# untitled.net
KiCad netlist of a schematic drawn in EAGLE
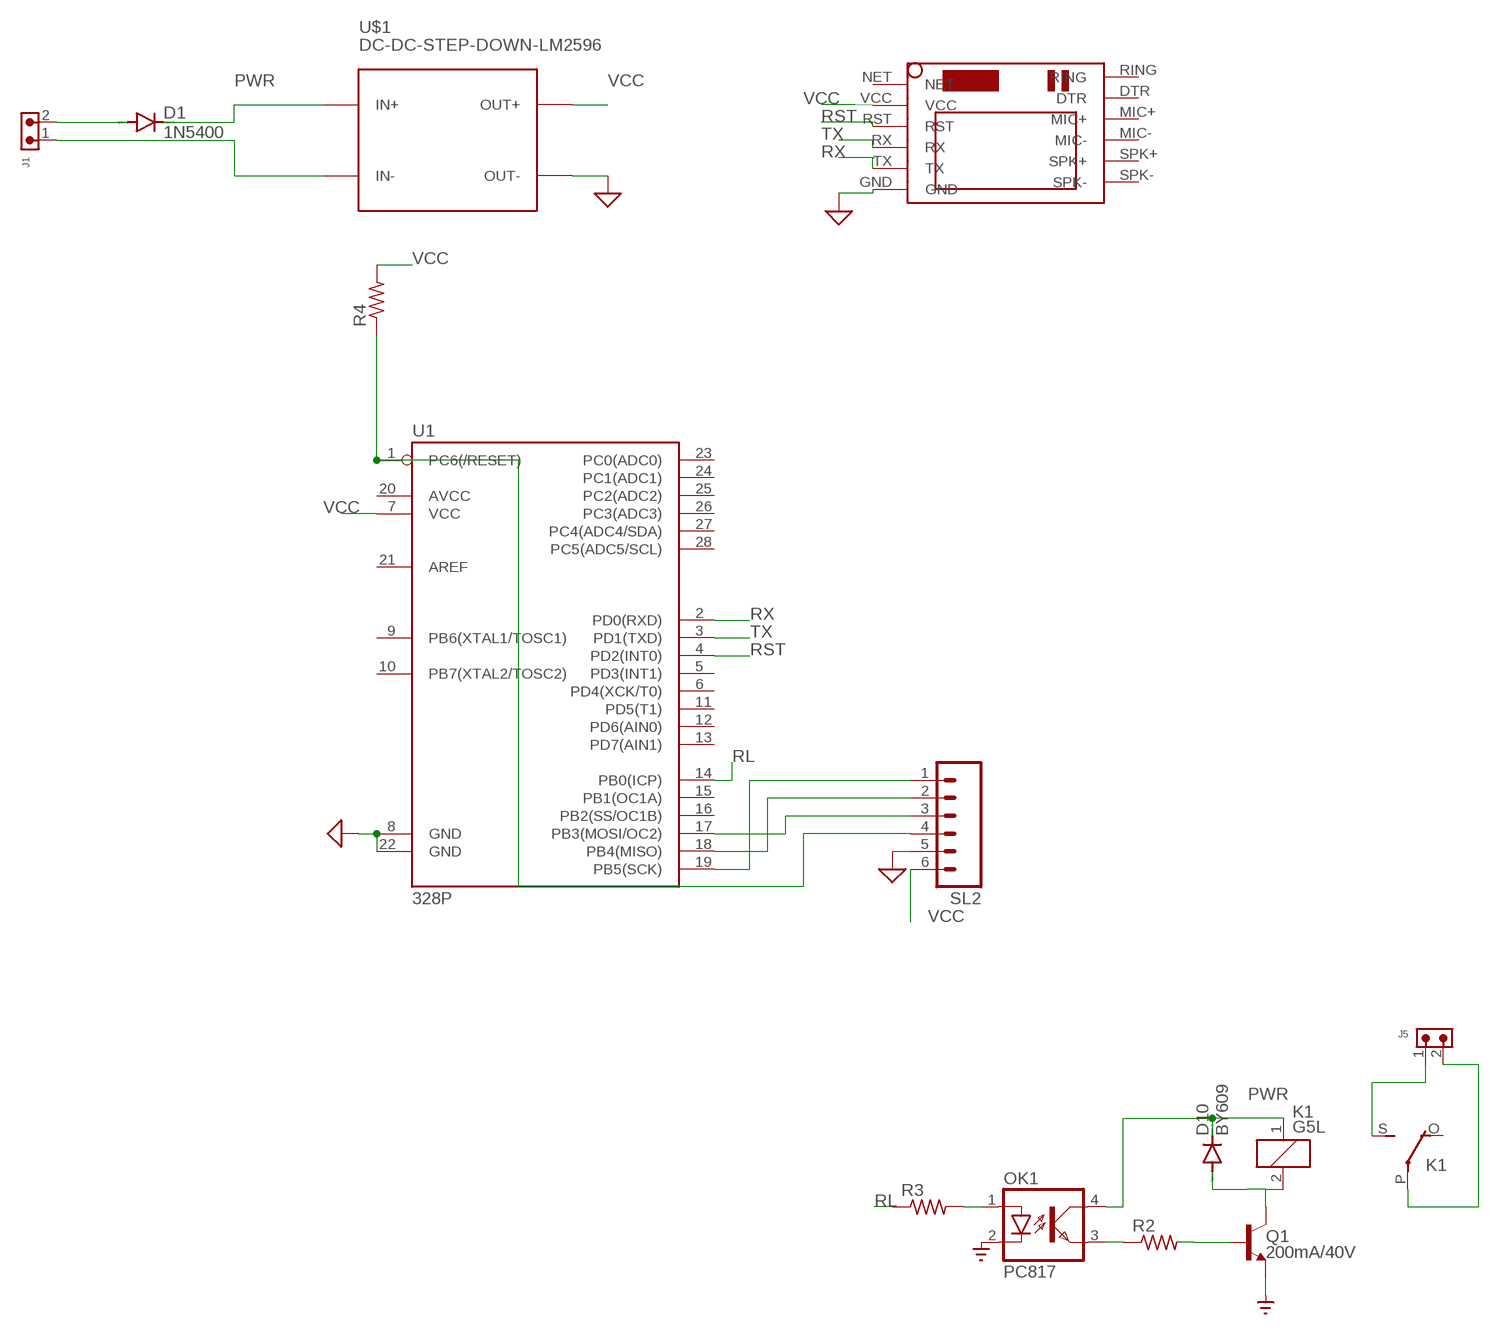
[diagram p0: schematic, sheet 1]

(export (version "E")
  (design (tool "Eeschema 10.0.6"))
  (components
    (comp (ref "D1")
      (value "1N5400")
      (footprint "eagle-import:DO201-15")
      (libsource (lib "eagle-import") (part "1N5400"))
    )
    (comp (ref "D10")
      (value "BY609")
      (footprint "eagle-import:SOD61B")
      (libsource (lib "eagle-import") (part "BY609"))
    )
    (comp (ref "J1")
      (value "691305530002")
      (footprint "eagle-import:691305530002")
      (libsource (lib "eagle-import") (part "691305530002"))
    )
    (comp (ref "J5")
      (value "691305530002")
      (footprint "eagle-import:691305530002")
      (libsource (lib "eagle-import") (part "691305530002"))
    )
    (comp (ref "K1")
      (value "G5L")
      (footprint "eagle-import:G5LE")
      (libsource (lib "eagle-import") (part "G5L"))
    )
    (comp (ref "OK1")
      (value "PC817")
      (footprint "eagle-import:DIL04")
      (fields (field (name "MPN") "PC817X4J000F"))
      (libsource (lib "eagle-import") (part "PC817"))
    )
    (comp (ref "Q1")
      (value "200mA/40V")
      (footprint "eagle-import:TO-92")
      (libsource (lib "eagle-import") (part "TRANS_NPN-2N3904"))
    )
    (comp (ref "R2")
      (value "R-US_0207/10")
      (footprint "eagle-import:0207_10")
      (libsource (lib "eagle-import") (part "R-US_0207/10"))
    )
    (comp (ref "R3")
      (value "R-US_0207/7")
      (footprint "eagle-import:0207_7")
      (libsource (lib "eagle-import") (part "adafruit_R-US_0207/7"))
    )
    (comp (ref "R4")
      (value "R-US_0207/10")
      (footprint "eagle-import:0207_10")
      (libsource (lib "eagle-import") (part "R-US_0207/10"))
    )
    (comp (ref "SL2")
      (value "M06")
      (footprint "eagle-import:06P")
      (libsource (lib "eagle-import") (part "M06"))
    )
    (comp (ref "U$1")
      (value "DC-DC-STEP-DOWN-LM2596")
      (footprint "eagle-import:DC-DC-STEP-DOWN-LM2596")
      (libsource (lib "eagle-import") (part "DC-DC-STEP-DOWN-LM2596"))
    )
    (comp (ref "U$2")
      (value "SIM800LMODULE")
      (footprint "eagle-import:SIM800LMODULE")
      (libsource (lib "eagle-import") (part "SIM800LMODULE"))
    )
    (comp (ref "U1")
      (value "328P")
      (footprint "eagle-import:DIP28")
      (libsource (lib "eagle-import") (part "ATMEGA328P_PDIP"))
    )
  )
  (nets
    (net (code "1") (name "/PWR") (class "Default")
      (node (ref "D1") (pin "C") (pinfunction "C_C") (pintype "passive"))
      (node (ref "D10") (pin "C") (pinfunction "C_C") (pintype "passive"))
      (node (ref "K1") (pin "1") (pinfunction "1_1") (pintype "passive"))
      (node (ref "OK1") (pin "4") (pinfunction "COL_4") (pintype "passive"))
      (node (ref "U$1") (pin "IN+") (pinfunction "IN+_IN+") (pintype "bidirectional"))
    )
    (net (code "2") (name "/RL") (class "Default")
      (node (ref "R3") (pin "1") (pinfunction "1_1") (pintype "passive"))
      (node (ref "U1") (pin "14") (pinfunction "PB0(ICP)_14") (pintype "bidirectional"))
    )
    (net (code "3") (name "/RST") (class "Default")
      (node (ref "U$2") (pin "RST") (pinfunction "RST_RST") (pintype "bidirectional"))
      (node (ref "U1") (pin "4") (pinfunction "PD2(INT0)_4") (pintype "bidirectional"))
    )
    (net (code "4") (name "/RX") (class "Default")
      (node (ref "U$2") (pin "TX") (pinfunction "TX_TX") (pintype "bidirectional"))
      (node (ref "U1") (pin "2") (pinfunction "PD0(RXD)_2") (pintype "bidirectional"))
    )
    (net (code "5") (name "/TX") (class "Default")
      (node (ref "U$2") (pin "RX") (pinfunction "RX_RX") (pintype "bidirectional"))
      (node (ref "U1") (pin "3") (pinfunction "PD1(TXD)_3") (pintype "bidirectional"))
    )
    (net (code "6") (name "/VCC") (class "Default")
      (node (ref "R4") (pin "2") (pinfunction "2_2") (pintype "passive"))
      (node (ref "SL2") (pin "6") (pinfunction "6_6") (pintype "passive"))
      (node (ref "U$1") (pin "OUT+") (pinfunction "OUT+_OUT+") (pintype "bidirectional"))
      (node (ref "U$2") (pin "VCC") (pinfunction "VCC_VCC") (pintype "bidirectional"))
      (node (ref "U1") (pin "7") (pinfunction "VCC_7") (pintype "bidirectional"))
    )
    (net (code "7") (name "Net-(D1-PadA)") (class "Default")
      (node (ref "D1") (pin "A") (pinfunction "A_A") (pintype "passive"))
      (node (ref "J1") (pin "2") (pinfunction "2_2") (pintype "passive"))
    )
    (net (code "8") (name "Net-(J1-Pad1)") (class "Default")
      (node (ref "J1") (pin "1") (pinfunction "1_1") (pintype "passive"))
      (node (ref "U$1") (pin "IN-") (pinfunction "IN-_IN-") (pintype "bidirectional"))
    )
    (net (code "9") (name "Net-(J5-Pad1)") (class "Default")
      (node (ref "J5") (pin "1") (pinfunction "1_1") (pintype "passive"))
      (node (ref "K1") (pin "S") (pinfunction "S_S") (pintype "passive"))
    )
    (net (code "10") (name "Net-(J5-Pad2)") (class "Default")
      (node (ref "J5") (pin "2") (pinfunction "2_2") (pintype "passive"))
      (node (ref "K1") (pin "P") (pinfunction "P_P") (pintype "passive"))
    )
    (net (code "11") (name "Net-(OK1-A)") (class "Default")
      (node (ref "OK1") (pin "1") (pinfunction "A_1") (pintype "passive"))
      (node (ref "R3") (pin "2") (pinfunction "2_2") (pintype "passive"))
    )
    (net (code "12") (name "Net-(OK1-EMIT)") (class "Default")
      (node (ref "OK1") (pin "3") (pinfunction "EMIT_3") (pintype "passive"))
      (node (ref "R2") (pin "1") (pinfunction "1_1") (pintype "passive"))
    )
    (net (code "13") (name "Net-(Q1-B)") (class "Default")
      (node (ref "Q1") (pin "2") (pinfunction "B_2") (pintype "passive"))
      (node (ref "R2") (pin "2") (pinfunction "2_2") (pintype "passive"))
    )
    (net (code "14") (name "Net-(Q1-C)") (class "Default")
      (node (ref "D10") (pin "A") (pinfunction "A_A") (pintype "passive"))
      (node (ref "K1") (pin "2") (pinfunction "2_2") (pintype "passive"))
      (node (ref "Q1") (pin "3") (pinfunction "C_3") (pintype "passive"))
    )
    (net (code "15") (name "Net-(U1-PB3(MOSI{slash}OC2))") (class "Default")
      (node (ref "SL2") (pin "3") (pinfunction "3_3") (pintype "passive"))
      (node (ref "U1") (pin "17") (pinfunction "PB3(MOSI/OC2)_17") (pintype "bidirectional"))
    )
    (net (code "16") (name "Net-(U1-PB4(MISO))") (class "Default")
      (node (ref "SL2") (pin "2") (pinfunction "2_2") (pintype "passive"))
      (node (ref "U1") (pin "18") (pinfunction "PB4(MISO)_18") (pintype "bidirectional"))
    )
    (net (code "17") (name "Net-(U1-PB5(SCK))") (class "Default")
      (node (ref "SL2") (pin "1") (pinfunction "1_1") (pintype "passive"))
      (node (ref "U1") (pin "19") (pinfunction "PB5(SCK)_19") (pintype "bidirectional"))
    )
    (net (code "18") (name "Net-(U1-PC6({slash}RESET))") (class "Default")
      (node (ref "R4") (pin "1") (pinfunction "1_1") (pintype "passive"))
      (node (ref "SL2") (pin "4") (pinfunction "4_4") (pintype "passive"))
      (node (ref "U1") (pin "1") (pinfunction "PC6(/RESET)_1") (pintype "bidirectional"))
    )
    (net (code "19") (name "SUP") (class "Default")
      (node (ref "OK1") (pin "2") (pinfunction "C_2") (pintype "passive"))
      (node (ref "Q1") (pin "1") (pinfunction "E_1") (pintype "passive"))
      (node (ref "SL2") (pin "5") (pinfunction "5_5") (pintype "passive"))
      (node (ref "U$1") (pin "OUT-") (pinfunction "OUT-_OUT-") (pintype "bidirectional"))
      (node (ref "U$2") (pin "GND") (pinfunction "GND_GND") (pintype "bidirectional"))
      (node (ref "U1") (pin "22") (pinfunction "GND_22") (pintype "bidirectional"))
      (node (ref "U1") (pin "8") (pinfunction "GND_8") (pintype "bidirectional"))
    )
    (net (code "20") (name "unconnected-(K1-PadO)") (class "Default")
      (node (ref "K1") (pin "O") (pinfunction "O_O") (pintype "passive"))
    )
    (net (code "21") (name "unconnected-(U$2-PadDTR)") (class "Default")
      (node (ref "U$2") (pin "DTR") (pinfunction "DTR_DTR") (pintype "bidirectional"))
    )
    (net (code "22") (name "unconnected-(U$2-PadMIC+)") (class "Default")
      (node (ref "U$2") (pin "MIC+") (pinfunction "MIC+_MIC+") (pintype "bidirectional"))
    )
    (net (code "23") (name "unconnected-(U$2-PadMIC-)") (class "Default")
      (node (ref "U$2") (pin "MIC-") (pinfunction "MIC-_MIC-") (pintype "bidirectional"))
    )
    (net (code "24") (name "unconnected-(U$2-PadNET)") (class "Default")
      (node (ref "U$2") (pin "NET") (pinfunction "NET_NET") (pintype "bidirectional"))
    )
    (net (code "25") (name "unconnected-(U$2-PadRING)") (class "Default")
      (node (ref "U$2") (pin "RING") (pinfunction "RING_RING") (pintype "bidirectional"))
    )
    (net (code "26") (name "unconnected-(U$2-PadSPK+)") (class "Default")
      (node (ref "U$2") (pin "SPK+") (pinfunction "SPK+_SPK+") (pintype "bidirectional"))
    )
    (net (code "27") (name "unconnected-(U$2-PadSPK-)") (class "Default")
      (node (ref "U$2") (pin "SPK-") (pinfunction "SPK-_SPK-") (pintype "bidirectional"))
    )
    (net (code "28") (name "unconnected-(U1-AREF-Pad21)") (class "Default")
      (node (ref "U1") (pin "21") (pinfunction "AREF_21") (pintype "bidirectional"))
    )
    (net (code "29") (name "unconnected-(U1-AVCC-Pad20)") (class "Default")
      (node (ref "U1") (pin "20") (pinfunction "AVCC_20") (pintype "bidirectional"))
    )
    (net (code "30") (name "unconnected-(U1-PB1(OC1A)-Pad15)") (class "Default")
      (node (ref "U1") (pin "15") (pinfunction "PB1(OC1A)_15") (pintype "bidirectional"))
    )
    (net (code "31") (name "unconnected-(U1-PB2(SS{slash}OC1B)-Pad16)") (class "Default")
      (node (ref "U1") (pin "16") (pinfunction "PB2(SS/OC1B)_16") (pintype "bidirectional"))
    )
    (net (code "32") (name "unconnected-(U1-PB6(XTAL1{slash}TOSC1)-Pad9)") (class "Default")
      (node (ref "U1") (pin "9") (pinfunction "PB6(XTAL1/TOSC1)_9") (pintype "bidirectional"))
    )
    (net (code "33") (name "unconnected-(U1-PB7(XTAL2{slash}TOSC2)-Pad10)") (class "Default")
      (node (ref "U1") (pin "10") (pinfunction "PB7(XTAL2/TOSC2)_10") (pintype "bidirectional"))
    )
    (net (code "34") (name "unconnected-(U1-PC0(ADC0)-Pad23)") (class "Default")
      (node (ref "U1") (pin "23") (pinfunction "PC0(ADC0)_23") (pintype "bidirectional"))
    )
    (net (code "35") (name "unconnected-(U1-PC1(ADC1)-Pad24)") (class "Default")
      (node (ref "U1") (pin "24") (pinfunction "PC1(ADC1)_24") (pintype "bidirectional"))
    )
    (net (code "36") (name "unconnected-(U1-PC2(ADC2)-Pad25)") (class "Default")
      (node (ref "U1") (pin "25") (pinfunction "PC2(ADC2)_25") (pintype "bidirectional"))
    )
    (net (code "37") (name "unconnected-(U1-PC3(ADC3)-Pad26)") (class "Default")
      (node (ref "U1") (pin "26") (pinfunction "PC3(ADC3)_26") (pintype "bidirectional"))
    )
    (net (code "38") (name "unconnected-(U1-PC4(ADC4{slash}SDA)-Pad27)") (class "Default")
      (node (ref "U1") (pin "27") (pinfunction "PC4(ADC4/SDA)_27") (pintype "bidirectional"))
    )
    (net (code "39") (name "unconnected-(U1-PC5(ADC5{slash}SCL)-Pad28)") (class "Default")
      (node (ref "U1") (pin "28") (pinfunction "PC5(ADC5/SCL)_28") (pintype "bidirectional"))
    )
    (net (code "40") (name "unconnected-(U1-PD3(INT1)-Pad5)") (class "Default")
      (node (ref "U1") (pin "5") (pinfunction "PD3(INT1)_5") (pintype "bidirectional"))
    )
    (net (code "41") (name "unconnected-(U1-PD4(XCK{slash}T0)-Pad6)") (class "Default")
      (node (ref "U1") (pin "6") (pinfunction "PD4(XCK/T0)_6") (pintype "bidirectional"))
    )
    (net (code "42") (name "unconnected-(U1-PD5(T1)-Pad11)") (class "Default")
      (node (ref "U1") (pin "11") (pinfunction "PD5(T1)_11") (pintype "bidirectional"))
    )
    (net (code "43") (name "unconnected-(U1-PD6(AIN0)-Pad12)") (class "Default")
      (node (ref "U1") (pin "12") (pinfunction "PD6(AIN0)_12") (pintype "bidirectional"))
    )
    (net (code "44") (name "unconnected-(U1-PD7(AIN1)-Pad13)") (class "Default")
      (node (ref "U1") (pin "13") (pinfunction "PD7(AIN1)_13") (pintype "bidirectional"))
    )
  )
)
